# MCU_v2.net
KiCad netlist of a schematic drawn in EAGLE
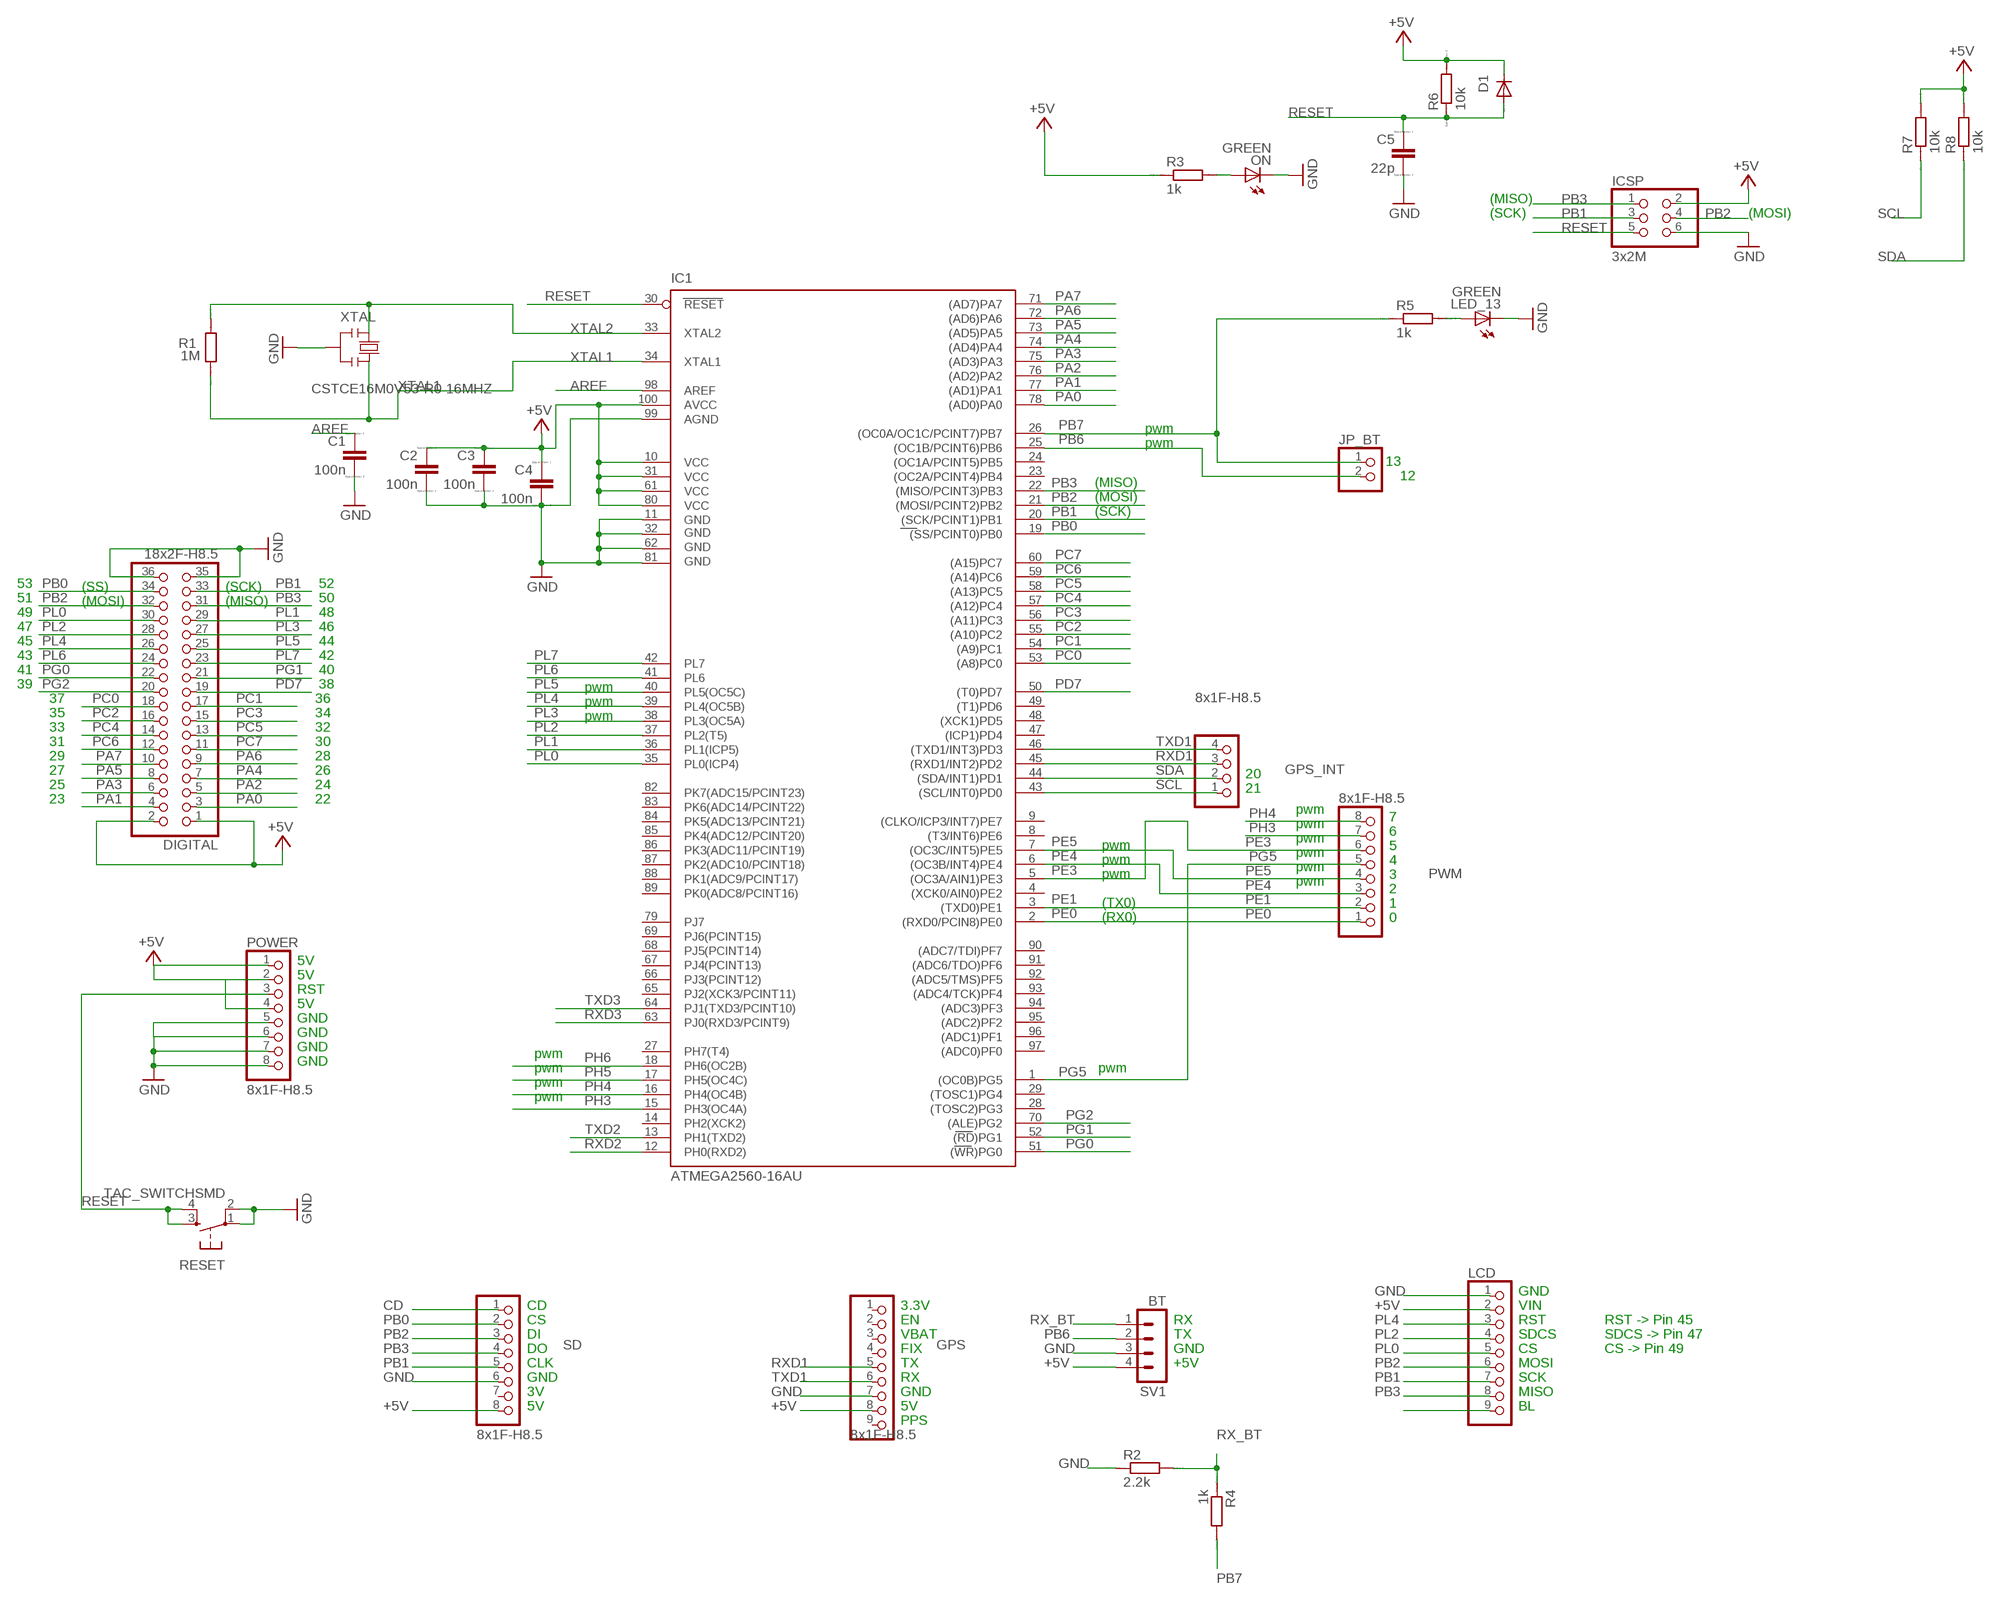
[diagram p0: schematic, sheet 1]

(export (version "E")
  (design (tool "Eeschema 10.0.6"))
  (components
    (comp (ref "C1")
      (value "100n")
      (footprint "eagle-import:C0805")
      (libsource (lib "eagle-import") (part "C-EUC0805"))
    )
    (comp (ref "C2")
      (value "100n")
      (footprint "eagle-import:C0805")
      (libsource (lib "eagle-import") (part "C-EUC0805"))
    )
    (comp (ref "C3")
      (value "100n")
      (footprint "eagle-import:C0805")
      (libsource (lib "eagle-import") (part "C-EUC0805"))
    )
    (comp (ref "C4")
      (value "100n")
      (footprint "eagle-import:C0805")
      (libsource (lib "eagle-import") (part "C-EUC0805"))
    )
    (comp (ref "C5")
      (value "22p")
      (footprint "eagle-import:C0805")
      (libsource (lib "eagle-import") (part "C-EUC0805"))
    )
    (comp (ref "D1")
      (value "DIODE-MINIMELF")
      (footprint "eagle-import:MINIMELF")
      (libsource (lib "eagle-import") (part "DIODE-MINIMELF"))
    )
    (comp (ref "DIGITAL")
      (value "18x2F-H8.5")
      (footprint "eagle-import:2X18")
      (libsource (lib "eagle-import") (part "PINHD-2X18"))
    )
    (comp (ref "GPS")
      (value "8x1F-H8.5")
      (footprint "eagle-import:1X09")
      (libsource (lib "eagle-import") (part "PINHD-1X9"))
    )
    (comp (ref "GPS_INT")
      (value "8x1F-H8.5")
      (footprint "eagle-import:1X04")
      (libsource (lib "eagle-import") (part "PINHD-1X4"))
    )
    (comp (ref "IC1")
      (value "ATMEGA2560-16AU")
      (footprint "eagle-import:TQFP100")
      (libsource (lib "eagle-import") (part "ATMEGA2560AU2560-16"))
    )
    (comp (ref "ICSP")
      (value "3x2M")
      (footprint "eagle-import:2X03")
      (libsource (lib "eagle-import") (part "PINHD-2X3"))
    )
    (comp (ref "JP_BT")
      (value "PINHD-1X2")
      (footprint "eagle-import:1X02")
      (libsource (lib "eagle-import") (part "PINHD-1X2"))
    )
    (comp (ref "LCD")
      (value "PINHD-1X9")
      (footprint "eagle-import:1X09")
      (libsource (lib "eagle-import") (part "PINHD-1X9"))
    )
    (comp (ref "LED_13")
      (value "GREEN")
      (footprint "eagle-import:CHIP-LED0805")
      (libsource (lib "eagle-import") (part "LEDCHIP-LED0805"))
    )
    (comp (ref "ON")
      (value "GREEN")
      (footprint "eagle-import:CHIP-LED0805")
      (libsource (lib "eagle-import") (part "LEDCHIP-LED0805"))
    )
    (comp (ref "POWER")
      (value "8x1F-H8.5")
      (footprint "eagle-import:1X08")
      (libsource (lib "eagle-import") (part "PINHD-1X8"))
    )
    (comp (ref "PWM")
      (value "8x1F-H8.5")
      (footprint "eagle-import:1X08")
      (libsource (lib "eagle-import") (part "PINHD-1X8"))
    )
    (comp (ref "R1")
      (value "1M")
      (footprint "eagle-import:R0805")
      (libsource (lib "eagle-import") (part "R-EU_R0805"))
    )
    (comp (ref "R2")
      (value "2.2k")
      (footprint "eagle-import:R0805")
      (libsource (lib "eagle-import") (part "R-EU_R0805"))
    )
    (comp (ref "R3")
      (value "1k")
      (footprint "eagle-import:R0805")
      (libsource (lib "eagle-import") (part "R-EU_R0805"))
    )
    (comp (ref "R4")
      (value "1k")
      (footprint "eagle-import:R0805")
      (libsource (lib "eagle-import") (part "R-EU_R0805"))
    )
    (comp (ref "R5")
      (value "1k")
      (footprint "eagle-import:R0805")
      (libsource (lib "eagle-import") (part "R-EU_R0805"))
    )
    (comp (ref "R6")
      (value "10k")
      (footprint "eagle-import:R0805")
      (libsource (lib "eagle-import") (part "R-EU_R0805"))
    )
    (comp (ref "R7")
      (value "10k")
      (footprint "eagle-import:R0805")
      (libsource (lib "eagle-import") (part "R-EU_R0805"))
    )
    (comp (ref "R8")
      (value "10k")
      (footprint "eagle-import:R0805")
      (libsource (lib "eagle-import") (part "R-EU_R0805"))
    )
    (comp (ref "RESET")
      (value "TAC_SWITCHSMD")
      (footprint "eagle-import:TACTILE-SWITCH-SMD")
      (libsource (lib "eagle-import") (part "TAC_SWITCHSMD"))
    )
    (comp (ref "SD")
      (value "8x1F-H8.5")
      (footprint "eagle-import:1X08")
      (libsource (lib "eagle-import") (part "PINHD-1X8"))
    )
    (comp (ref "SV1")
      (value "BT")
      (footprint "eagle-import:MA04-1")
      (libsource (lib "eagle-import") (part "MA04-1"))
    )
    (comp (ref "XTAL")
      (value "CSTCE16M0V53-R0 16MHZ")
      (footprint "eagle-import:RESONATOR")
      (libsource (lib "eagle-import") (part "RESONATORMU"))
    )
  )
  (nets
    (net (code "1") (name "+5V") (class "Default")
      (node (ref "C2") (pin "1") (pinfunction "1_1") (pintype "passive"))
      (node (ref "C3") (pin "1") (pinfunction "1_1") (pintype "passive"))
      (node (ref "C4") (pin "1") (pinfunction "1_1") (pintype "passive"))
      (node (ref "D1") (pin "C") (pinfunction "C_C") (pintype "passive"))
      (node (ref "DIGITAL") (pin "1") (pinfunction "1_1") (pintype "passive"))
      (node (ref "DIGITAL") (pin "2") (pinfunction "2_2") (pintype "passive"))
      (node (ref "GPS") (pin "8") (pinfunction "8_8") (pintype "passive"))
      (node (ref "IC1") (pin "10") (pinfunction "VCC_10") (pintype "power_in"))
      (node (ref "IC1") (pin "100") (pinfunction "AVCC_100") (pintype "power_in"))
      (node (ref "IC1") (pin "31") (pinfunction "VCC1_31") (pintype "power_in"))
      (node (ref "IC1") (pin "61") (pinfunction "VCC2_61") (pintype "power_in"))
      (node (ref "IC1") (pin "80") (pinfunction "VCC3_80") (pintype "power_in"))
      (node (ref "ICSP") (pin "2") (pinfunction "2_2") (pintype "passive"))
      (node (ref "LCD") (pin "2") (pinfunction "2_2") (pintype "passive"))
      (node (ref "POWER") (pin "1") (pinfunction "1_1") (pintype "passive"))
      (node (ref "POWER") (pin "2") (pinfunction "2_2") (pintype "passive"))
      (node (ref "POWER") (pin "4") (pinfunction "4_4") (pintype "passive"))
      (node (ref "R3") (pin "1") (pinfunction "1_1") (pintype "passive"))
      (node (ref "R6") (pin "2") (pinfunction "2_2") (pintype "passive"))
      (node (ref "R7") (pin "2") (pinfunction "2_2") (pintype "passive"))
      (node (ref "R8") (pin "2") (pinfunction "2_2") (pintype "passive"))
      (node (ref "SD") (pin "8") (pinfunction "8_8") (pintype "passive"))
      (node (ref "SV1") (pin "4") (pinfunction "4_4") (pintype "passive"))
    )
    (net (code "2") (name "/AREF") (class "Default")
      (node (ref "C1") (pin "1") (pinfunction "1_1") (pintype "passive"))
      (node (ref "IC1") (pin "98") (pinfunction "AREF_98") (pintype "bidirectional"))
    )
    (net (code "3") (name "/CD") (class "Default")
      (node (ref "SD") (pin "1") (pinfunction "1_1") (pintype "passive"))
    )
    (net (code "4") (name "/PA0") (class "Default")
      (node (ref "DIGITAL") (pin "3") (pinfunction "3_3") (pintype "passive"))
      (node (ref "IC1") (pin "78") (pinfunction "(AD0)PA0_78") (pintype "bidirectional"))
    )
    (net (code "5") (name "/PA1") (class "Default")
      (node (ref "DIGITAL") (pin "4") (pinfunction "4_4") (pintype "passive"))
      (node (ref "IC1") (pin "77") (pinfunction "(AD1)PA1_77") (pintype "bidirectional"))
    )
    (net (code "6") (name "/PA2") (class "Default")
      (node (ref "DIGITAL") (pin "5") (pinfunction "5_5") (pintype "passive"))
      (node (ref "IC1") (pin "76") (pinfunction "(AD2)PA2_76") (pintype "bidirectional"))
    )
    (net (code "7") (name "/PA3") (class "Default")
      (node (ref "DIGITAL") (pin "6") (pinfunction "6_6") (pintype "passive"))
      (node (ref "IC1") (pin "75") (pinfunction "(AD3)PA3_75") (pintype "bidirectional"))
    )
    (net (code "8") (name "/PA4") (class "Default")
      (node (ref "DIGITAL") (pin "7") (pinfunction "7_7") (pintype "passive"))
      (node (ref "IC1") (pin "74") (pinfunction "(AD4)PA4_74") (pintype "bidirectional"))
    )
    (net (code "9") (name "/PA5") (class "Default")
      (node (ref "DIGITAL") (pin "8") (pinfunction "8_8") (pintype "passive"))
      (node (ref "IC1") (pin "73") (pinfunction "(AD5)PA5_73") (pintype "bidirectional"))
    )
    (net (code "10") (name "/PA6") (class "Default")
      (node (ref "DIGITAL") (pin "9") (pinfunction "9_9") (pintype "passive"))
      (node (ref "IC1") (pin "72") (pinfunction "(AD6)PA6_72") (pintype "bidirectional"))
    )
    (net (code "11") (name "/PA7") (class "Default")
      (node (ref "DIGITAL") (pin "10") (pinfunction "10_10") (pintype "passive"))
      (node (ref "IC1") (pin "71") (pinfunction "(AD7)PA7_71") (pintype "bidirectional"))
    )
    (net (code "12") (name "/PB0") (class "Default")
      (node (ref "DIGITAL") (pin "34") (pinfunction "34_34") (pintype "passive"))
      (node (ref "IC1") (pin "19") (pinfunction "(SS/PCINT0)PB0_19") (pintype "bidirectional"))
      (node (ref "SD") (pin "2") (pinfunction "2_2") (pintype "passive"))
    )
    (net (code "13") (name "/PB1") (class "Default")
      (node (ref "DIGITAL") (pin "33") (pinfunction "33_33") (pintype "passive"))
      (node (ref "IC1") (pin "20") (pinfunction "(SCK/PCINT1)PB1_20") (pintype "bidirectional"))
      (node (ref "ICSP") (pin "3") (pinfunction "3_3") (pintype "passive"))
      (node (ref "LCD") (pin "7") (pinfunction "7_7") (pintype "passive"))
      (node (ref "SD") (pin "5") (pinfunction "5_5") (pintype "passive"))
    )
    (net (code "14") (name "/PB2") (class "Default")
      (node (ref "DIGITAL") (pin "32") (pinfunction "32_32") (pintype "passive"))
      (node (ref "IC1") (pin "21") (pinfunction "(MOSI/PCINT2)PB2_21") (pintype "bidirectional"))
      (node (ref "ICSP") (pin "4") (pinfunction "4_4") (pintype "passive"))
      (node (ref "LCD") (pin "6") (pinfunction "6_6") (pintype "passive"))
      (node (ref "SD") (pin "3") (pinfunction "3_3") (pintype "passive"))
    )
    (net (code "15") (name "/PB3") (class "Default")
      (node (ref "DIGITAL") (pin "31") (pinfunction "31_31") (pintype "passive"))
      (node (ref "IC1") (pin "22") (pinfunction "(MISO/PCINT3)PB3_22") (pintype "bidirectional"))
      (node (ref "ICSP") (pin "1") (pinfunction "1_1") (pintype "passive"))
      (node (ref "LCD") (pin "8") (pinfunction "8_8") (pintype "passive"))
      (node (ref "SD") (pin "4") (pinfunction "4_4") (pintype "passive"))
    )
    (net (code "16") (name "/PB6") (class "Default")
      (node (ref "IC1") (pin "25") (pinfunction "(OC1B/PCINT6)PB6_25") (pintype "bidirectional"))
      (node (ref "JP_BT") (pin "2") (pinfunction "2_2") (pintype "passive"))
      (node (ref "SV1") (pin "2") (pinfunction "2_2") (pintype "passive"))
    )
    (net (code "17") (name "/PB7") (class "Default")
      (node (ref "IC1") (pin "26") (pinfunction "(OC0A/OC1C/PCINT7)PB7_26") (pintype "bidirectional"))
      (node (ref "JP_BT") (pin "1") (pinfunction "1_1") (pintype "passive"))
      (node (ref "R4") (pin "2") (pinfunction "2_2") (pintype "passive"))
      (node (ref "R5") (pin "1") (pinfunction "1_1") (pintype "passive"))
    )
    (net (code "18") (name "/PC0") (class "Default")
      (node (ref "DIGITAL") (pin "18") (pinfunction "18_18") (pintype "passive"))
      (node (ref "IC1") (pin "53") (pinfunction "(A8)PC0_53") (pintype "bidirectional"))
    )
    (net (code "19") (name "/PC1") (class "Default")
      (node (ref "DIGITAL") (pin "17") (pinfunction "17_17") (pintype "passive"))
      (node (ref "IC1") (pin "54") (pinfunction "(A9)PC1_54") (pintype "bidirectional"))
    )
    (net (code "20") (name "/PC2") (class "Default")
      (node (ref "DIGITAL") (pin "16") (pinfunction "16_16") (pintype "passive"))
      (node (ref "IC1") (pin "55") (pinfunction "(A10)PC2_55") (pintype "bidirectional"))
    )
    (net (code "21") (name "/PC3") (class "Default")
      (node (ref "DIGITAL") (pin "15") (pinfunction "15_15") (pintype "passive"))
      (node (ref "IC1") (pin "56") (pinfunction "(A11)PC3_56") (pintype "bidirectional"))
    )
    (net (code "22") (name "/PC4") (class "Default")
      (node (ref "DIGITAL") (pin "14") (pinfunction "14_14") (pintype "passive"))
      (node (ref "IC1") (pin "57") (pinfunction "(A12)PC4_57") (pintype "bidirectional"))
    )
    (net (code "23") (name "/PC5") (class "Default")
      (node (ref "DIGITAL") (pin "13") (pinfunction "13_13") (pintype "passive"))
      (node (ref "IC1") (pin "58") (pinfunction "(A13)PC5_58") (pintype "bidirectional"))
    )
    (net (code "24") (name "/PC6") (class "Default")
      (node (ref "DIGITAL") (pin "12") (pinfunction "12_12") (pintype "passive"))
      (node (ref "IC1") (pin "59") (pinfunction "(A14)PC6_59") (pintype "bidirectional"))
    )
    (net (code "25") (name "/PC7") (class "Default")
      (node (ref "DIGITAL") (pin "11") (pinfunction "11_11") (pintype "passive"))
      (node (ref "IC1") (pin "60") (pinfunction "(A15)PC7_60") (pintype "bidirectional"))
    )
    (net (code "26") (name "/PD7") (class "Default")
      (node (ref "DIGITAL") (pin "19") (pinfunction "19_19") (pintype "passive"))
      (node (ref "IC1") (pin "50") (pinfunction "(T0)PD7_50") (pintype "bidirectional"))
    )
    (net (code "27") (name "/PE0") (class "Default")
      (node (ref "IC1") (pin "2") (pinfunction "(RXD0/PCIN8)PE0_2") (pintype "bidirectional"))
      (node (ref "PWM") (pin "1") (pinfunction "1_1") (pintype "passive"))
    )
    (net (code "28") (name "/PE1") (class "Default")
      (node (ref "IC1") (pin "3") (pinfunction "(TXD0)PE1_3") (pintype "bidirectional"))
      (node (ref "PWM") (pin "2") (pinfunction "2_2") (pintype "passive"))
    )
    (net (code "29") (name "/PE3") (class "Default")
      (node (ref "IC1") (pin "5") (pinfunction "(OC3A/AIN1)PE3_5") (pintype "bidirectional"))
      (node (ref "PWM") (pin "6") (pinfunction "6_6") (pintype "passive"))
    )
    (net (code "30") (name "/PE4") (class "Default")
      (node (ref "IC1") (pin "6") (pinfunction "(OC3B/INT4)PE4_6") (pintype "bidirectional"))
      (node (ref "PWM") (pin "3") (pinfunction "3_3") (pintype "passive"))
    )
    (net (code "31") (name "/PE5") (class "Default")
      (node (ref "IC1") (pin "7") (pinfunction "(OC3C/INT5)PE5_7") (pintype "bidirectional"))
      (node (ref "PWM") (pin "4") (pinfunction "4_4") (pintype "passive"))
    )
    (net (code "32") (name "/PG0") (class "Default")
      (node (ref "DIGITAL") (pin "22") (pinfunction "22_22") (pintype "passive"))
      (node (ref "IC1") (pin "51") (pinfunction "(WR)PG0_51") (pintype "bidirectional"))
    )
    (net (code "33") (name "/PG1") (class "Default")
      (node (ref "DIGITAL") (pin "21") (pinfunction "21_21") (pintype "passive"))
      (node (ref "IC1") (pin "52") (pinfunction "(RD)PG1_52") (pintype "bidirectional"))
    )
    (net (code "34") (name "/PG2") (class "Default")
      (node (ref "DIGITAL") (pin "20") (pinfunction "20_20") (pintype "passive"))
      (node (ref "IC1") (pin "70") (pinfunction "(ALE)PG2_70") (pintype "bidirectional"))
    )
    (net (code "35") (name "/PG5") (class "Default")
      (node (ref "IC1") (pin "1") (pinfunction "(OC0B)PG5_1") (pintype "bidirectional"))
      (node (ref "PWM") (pin "5") (pinfunction "5_5") (pintype "passive"))
    )
    (net (code "36") (name "/PH3") (class "Default")
      (node (ref "IC1") (pin "15") (pinfunction "PH3(OC4A)_15") (pintype "bidirectional"))
      (node (ref "PWM") (pin "7") (pinfunction "7_7") (pintype "passive"))
    )
    (net (code "37") (name "/PH4") (class "Default")
      (node (ref "IC1") (pin "16") (pinfunction "PH4(OC4B)_16") (pintype "bidirectional"))
      (node (ref "PWM") (pin "8") (pinfunction "8_8") (pintype "passive"))
    )
    (net (code "38") (name "/PH5") (class "Default")
      (node (ref "IC1") (pin "17") (pinfunction "PH5(OC4C)_17") (pintype "bidirectional"))
    )
    (net (code "39") (name "/PH6") (class "Default")
      (node (ref "IC1") (pin "18") (pinfunction "PH6(OC2B)_18") (pintype "bidirectional"))
    )
    (net (code "40") (name "/PL0") (class "Default")
      (node (ref "DIGITAL") (pin "30") (pinfunction "30_30") (pintype "passive"))
      (node (ref "IC1") (pin "35") (pinfunction "PL0(ICP4)_35") (pintype "bidirectional"))
      (node (ref "LCD") (pin "5") (pinfunction "5_5") (pintype "passive"))
    )
    (net (code "41") (name "/PL1") (class "Default")
      (node (ref "DIGITAL") (pin "29") (pinfunction "29_29") (pintype "passive"))
      (node (ref "IC1") (pin "36") (pinfunction "PL1(ICP5)_36") (pintype "bidirectional"))
    )
    (net (code "42") (name "/PL2") (class "Default")
      (node (ref "DIGITAL") (pin "28") (pinfunction "28_28") (pintype "passive"))
      (node (ref "IC1") (pin "37") (pinfunction "PL2(T5)_37") (pintype "bidirectional"))
      (node (ref "LCD") (pin "4") (pinfunction "4_4") (pintype "passive"))
    )
    (net (code "43") (name "/PL3") (class "Default")
      (node (ref "DIGITAL") (pin "27") (pinfunction "27_27") (pintype "passive"))
      (node (ref "IC1") (pin "38") (pinfunction "PL3(OC5A)_38") (pintype "bidirectional"))
    )
    (net (code "44") (name "/PL4") (class "Default")
      (node (ref "DIGITAL") (pin "26") (pinfunction "26_26") (pintype "passive"))
      (node (ref "IC1") (pin "39") (pinfunction "PL4(OC5B)_39") (pintype "bidirectional"))
      (node (ref "LCD") (pin "3") (pinfunction "3_3") (pintype "passive"))
    )
    (net (code "45") (name "/PL5") (class "Default")
      (node (ref "DIGITAL") (pin "25") (pinfunction "25_25") (pintype "passive"))
      (node (ref "IC1") (pin "40") (pinfunction "PL5(OC5C)_40") (pintype "bidirectional"))
    )
    (net (code "46") (name "/PL6") (class "Default")
      (node (ref "DIGITAL") (pin "24") (pinfunction "24_24") (pintype "passive"))
      (node (ref "IC1") (pin "41") (pinfunction "PL6_41") (pintype "bidirectional"))
    )
    (net (code "47") (name "/PL7") (class "Default")
      (node (ref "DIGITAL") (pin "23") (pinfunction "23_23") (pintype "passive"))
      (node (ref "IC1") (pin "42") (pinfunction "PL7_42") (pintype "bidirectional"))
    )
    (net (code "48") (name "/RESET") (class "Default")
      (node (ref "C5") (pin "1") (pinfunction "1_1") (pintype "passive"))
      (node (ref "D1") (pin "A") (pinfunction "A_A") (pintype "passive"))
      (node (ref "IC1") (pin "30") (pinfunction "RESET_30") (pintype "input"))
      (node (ref "ICSP") (pin "5") (pinfunction "5_5") (pintype "passive"))
      (node (ref "POWER") (pin "3") (pinfunction "3_3") (pintype "passive"))
      (node (ref "R6") (pin "1") (pinfunction "1_1") (pintype "passive"))
      (node (ref "RESET") (pin "3") (pinfunction "3_3") (pintype "passive"))
      (node (ref "RESET") (pin "4") (pinfunction "4_4") (pintype "passive"))
    )
    (net (code "49") (name "/RXD1") (class "Default")
      (node (ref "GPS") (pin "5") (pinfunction "5_5") (pintype "passive"))
      (node (ref "GPS_INT") (pin "3") (pinfunction "3_3") (pintype "passive"))
      (node (ref "IC1") (pin "45") (pinfunction "(RXD1/INT2)PD2_45") (pintype "bidirectional"))
    )
    (net (code "50") (name "/RXD2") (class "Default")
      (node (ref "IC1") (pin "12") (pinfunction "PH0(RXD2)_12") (pintype "bidirectional"))
    )
    (net (code "51") (name "/RXD3") (class "Default")
      (node (ref "IC1") (pin "63") (pinfunction "PJ0(RXD3/PCINT9)_63") (pintype "bidirectional"))
    )
    (net (code "52") (name "/RX_BT") (class "Default")
      (node (ref "R2") (pin "2") (pinfunction "2_2") (pintype "passive"))
      (node (ref "R4") (pin "1") (pinfunction "1_1") (pintype "passive"))
      (node (ref "SV1") (pin "1") (pinfunction "1_1") (pintype "passive"))
    )
    (net (code "53") (name "/SCL") (class "Default")
      (node (ref "GPS_INT") (pin "1") (pinfunction "1_1") (pintype "passive"))
      (node (ref "IC1") (pin "43") (pinfunction "(SCL/INT0)PD0_43") (pintype "bidirectional"))
      (node (ref "R7") (pin "1") (pinfunction "1_1") (pintype "passive"))
    )
    (net (code "54") (name "/SDA") (class "Default")
      (node (ref "GPS_INT") (pin "2") (pinfunction "2_2") (pintype "passive"))
      (node (ref "IC1") (pin "44") (pinfunction "(SDA/INT1)PD1_44") (pintype "bidirectional"))
      (node (ref "R8") (pin "1") (pinfunction "1_1") (pintype "passive"))
    )
    (net (code "55") (name "/TXD1") (class "Default")
      (node (ref "GPS") (pin "6") (pinfunction "6_6") (pintype "passive"))
      (node (ref "GPS_INT") (pin "4") (pinfunction "4_4") (pintype "passive"))
      (node (ref "IC1") (pin "46") (pinfunction "(TXD1/INT3)PD3_46") (pintype "bidirectional"))
    )
    (net (code "56") (name "/TXD2") (class "Default")
      (node (ref "IC1") (pin "13") (pinfunction "PH1(TXD2)_13") (pintype "bidirectional"))
    )
    (net (code "57") (name "/TXD3") (class "Default")
      (node (ref "IC1") (pin "64") (pinfunction "PJ1(TXD3/PCINT10)_64") (pintype "bidirectional"))
    )
    (net (code "58") (name "/XTAL1") (class "Default")
      (node (ref "IC1") (pin "34") (pinfunction "XTAL1_34") (pintype "input"))
      (node (ref "R1") (pin "1") (pinfunction "1_1") (pintype "passive"))
      (node (ref "XTAL") (pin "3") (pinfunction "3_3") (pintype "passive"))
    )
    (net (code "59") (name "/XTAL2") (class "Default")
      (node (ref "IC1") (pin "33") (pinfunction "XTAL2_33") (pintype "output"))
      (node (ref "R1") (pin "2") (pinfunction "2_2") (pintype "passive"))
      (node (ref "XTAL") (pin "1") (pinfunction "1_1") (pintype "passive"))
    )
    (net (code "60") (name "GND") (class "Default")
      (node (ref "C1") (pin "2") (pinfunction "2_2") (pintype "passive"))
      (node (ref "C2") (pin "2") (pinfunction "2_2") (pintype "passive"))
      (node (ref "C3") (pin "2") (pinfunction "2_2") (pintype "passive"))
      (node (ref "C4") (pin "2") (pinfunction "2_2") (pintype "passive"))
      (node (ref "C5") (pin "2") (pinfunction "2_2") (pintype "passive"))
      (node (ref "DIGITAL") (pin "35") (pinfunction "35_35") (pintype "passive"))
      (node (ref "DIGITAL") (pin "36") (pinfunction "36_36") (pintype "passive"))
      (node (ref "GPS") (pin "7") (pinfunction "7_7") (pintype "passive"))
      (node (ref "IC1") (pin "11") (pinfunction "GND_11") (pintype "power_in"))
      (node (ref "IC1") (pin "32") (pinfunction "GND1_32") (pintype "power_in"))
      (node (ref "IC1") (pin "62") (pinfunction "GND2_62") (pintype "power_in"))
      (node (ref "IC1") (pin "81") (pinfunction "GND3_81") (pintype "power_in"))
      (node (ref "IC1") (pin "99") (pinfunction "AGND_99") (pintype "power_in"))
      (node (ref "ICSP") (pin "6") (pinfunction "6_6") (pintype "passive"))
      (node (ref "LCD") (pin "1") (pinfunction "1_1") (pintype "passive"))
      (node (ref "LED_13") (pin "C") (pinfunction "C_C") (pintype "passive"))
      (node (ref "ON") (pin "C") (pinfunction "C_C") (pintype "passive"))
      (node (ref "POWER") (pin "5") (pinfunction "5_5") (pintype "passive"))
      (node (ref "POWER") (pin "6") (pinfunction "6_6") (pintype "passive"))
      (node (ref "POWER") (pin "7") (pinfunction "7_7") (pintype "passive"))
      (node (ref "POWER") (pin "8") (pinfunction "8_8") (pintype "passive"))
      (node (ref "R2") (pin "1") (pinfunction "1_1") (pintype "passive"))
      (node (ref "RESET") (pin "1") (pinfunction "1_1") (pintype "passive"))
      (node (ref "RESET") (pin "2") (pinfunction "2_2") (pintype "passive"))
      (node (ref "SD") (pin "6") (pinfunction "6_6") (pintype "passive"))
      (node (ref "SV1") (pin "3") (pinfunction "3_3") (pintype "passive"))
      (node (ref "XTAL") (pin "2") (pinfunction "2_2") (pintype "passive"))
    )
    (net (code "61") (name "Net-(LED_13-PadA)") (class "Default")
      (node (ref "LED_13") (pin "A") (pinfunction "A_A") (pintype "passive"))
      (node (ref "R5") (pin "2") (pinfunction "2_2") (pintype "passive"))
    )
    (net (code "62") (name "Net-(ON-PadA)") (class "Default")
      (node (ref "ON") (pin "A") (pinfunction "A_A") (pintype "passive"))
      (node (ref "R3") (pin "2") (pinfunction "2_2") (pintype "passive"))
    )
    (net (code "63") (name "unconnected-(GPS-Pad1)") (class "Default")
      (node (ref "GPS") (pin "1") (pinfunction "1_1") (pintype "passive"))
    )
    (net (code "64") (name "unconnected-(GPS-Pad2)") (class "Default")
      (node (ref "GPS") (pin "2") (pinfunction "2_2") (pintype "passive"))
    )
    (net (code "65") (name "unconnected-(GPS-Pad3)") (class "Default")
      (node (ref "GPS") (pin "3") (pinfunction "3_3") (pintype "passive"))
    )
    (net (code "66") (name "unconnected-(GPS-Pad4)") (class "Default")
      (node (ref "GPS") (pin "4") (pinfunction "4_4") (pintype "passive"))
    )
    (net (code "67") (name "unconnected-(GPS-Pad9)") (class "Default")
      (node (ref "GPS") (pin "9") (pinfunction "9_9") (pintype "passive"))
    )
    (net (code "68") (name "unconnected-(IC1-(ADC0)PF0-Pad97)") (class "Default")
      (node (ref "IC1") (pin "97") (pinfunction "(ADC0)PF0_97") (pintype "bidirectional"))
    )
    (net (code "69") (name "unconnected-(IC1-(ADC1)PF1-Pad96)") (class "Default")
      (node (ref "IC1") (pin "96") (pinfunction "(ADC1)PF1_96") (pintype "bidirectional"))
    )
    (net (code "70") (name "unconnected-(IC1-(ADC2)PF2-Pad95)") (class "Default")
      (node (ref "IC1") (pin "95") (pinfunction "(ADC2)PF2_95") (pintype "bidirectional"))
    )
    (net (code "71") (name "unconnected-(IC1-(ADC3)PF3-Pad94)") (class "Default")
      (node (ref "IC1") (pin "94") (pinfunction "(ADC3)PF3_94") (pintype "bidirectional"))
    )
    (net (code "72") (name "unconnected-(IC1-(ADC4{slash}TCK)PF4-Pad93)") (class "Default")
      (node (ref "IC1") (pin "93") (pinfunction "(ADC4/TCK)PF4_93") (pintype "bidirectional"))
    )
    (net (code "73") (name "unconnected-(IC1-(ADC5{slash}TMS)PF5-Pad92)") (class "Default")
      (node (ref "IC1") (pin "92") (pinfunction "(ADC5/TMS)PF5_92") (pintype "bidirectional"))
    )
    (net (code "74") (name "unconnected-(IC1-(ADC6{slash}TDO)PF6-Pad91)") (class "Default")
      (node (ref "IC1") (pin "91") (pinfunction "(ADC6/TDO)PF6_91") (pintype "bidirectional"))
    )
    (net (code "75") (name "unconnected-(IC1-(ADC7{slash}TDI)PF7-Pad90)") (class "Default")
      (node (ref "IC1") (pin "90") (pinfunction "(ADC7/TDI)PF7_90") (pintype "bidirectional"))
    )
    (net (code "76") (name "unconnected-(IC1-(CLKO{slash}ICP3{slash}INT7)PE7-Pad9)") (class "Default")
      (node (ref "IC1") (pin "9") (pinfunction "(CLKO/ICP3/INT7)PE7_9") (pintype "bidirectional"))
    )
    (net (code "77") (name "unconnected-(IC1-(ICP1)PD4-Pad47)") (class "Default")
      (node (ref "IC1") (pin "47") (pinfunction "(ICP1)PD4_47") (pintype "bidirectional"))
    )
    (net (code "78") (name "unconnected-(IC1-(OC1A{slash}PCINT5)PB5-Pad24)") (class "Default")
      (node (ref "IC1") (pin "24") (pinfunction "(OC1A/PCINT5)PB5_24") (pintype "bidirectional"))
    )
    (net (code "79") (name "unconnected-(IC1-(OC2A{slash}PCINT4)PB4-Pad23)") (class "Default")
      (node (ref "IC1") (pin "23") (pinfunction "(OC2A/PCINT4)PB4_23") (pintype "bidirectional"))
    )
    (net (code "80") (name "unconnected-(IC1-(T1)PD6-Pad49)") (class "Default")
      (node (ref "IC1") (pin "49") (pinfunction "(T1)PD6_49") (pintype "bidirectional"))
    )
    (net (code "81") (name "unconnected-(IC1-(T3{slash}INT6)PE6-Pad8)") (class "Default")
      (node (ref "IC1") (pin "8") (pinfunction "(T3/INT6)PE6_8") (pintype "bidirectional"))
    )
    (net (code "82") (name "unconnected-(IC1-(TOSC1)PG4-Pad29)") (class "Default")
      (node (ref "IC1") (pin "29") (pinfunction "(TOSC1)PG4_29") (pintype "bidirectional"))
    )
    (net (code "83") (name "unconnected-(IC1-(TOSC2)PG3-Pad28)") (class "Default")
      (node (ref "IC1") (pin "28") (pinfunction "(TOSC2)PG3_28") (pintype "bidirectional"))
    )
    (net (code "84") (name "unconnected-(IC1-(XCK0{slash}AIN0)PE2-Pad4)") (class "Default")
      (node (ref "IC1") (pin "4") (pinfunction "(XCK0/AIN0)PE2_4") (pintype "bidirectional"))
    )
    (net (code "85") (name "unconnected-(IC1-(XCK1)PD5-Pad48)") (class "Default")
      (node (ref "IC1") (pin "48") (pinfunction "(XCK1)PD5_48") (pintype "bidirectional"))
    )
    (net (code "86") (name "unconnected-(IC1-PH2(XCK2)-Pad14)") (class "Default")
      (node (ref "IC1") (pin "14") (pinfunction "PH2(XCK2)_14") (pintype "bidirectional"))
    )
    (net (code "87") (name "unconnected-(IC1-PH7(T4)-Pad27)") (class "Default")
      (node (ref "IC1") (pin "27") (pinfunction "PH7(T4)_27") (pintype "bidirectional"))
    )
    (net (code "88") (name "unconnected-(IC1-PJ2(XCK3{slash}PCINT11)-Pad65)") (class "Default")
      (node (ref "IC1") (pin "65") (pinfunction "PJ2(XCK3/PCINT11)_65") (pintype "bidirectional"))
    )
    (net (code "89") (name "unconnected-(IC1-PJ3(PCINT12)-Pad66)") (class "Default")
      (node (ref "IC1") (pin "66") (pinfunction "PJ3(PCINT12)_66") (pintype "bidirectional"))
    )
    (net (code "90") (name "unconnected-(IC1-PJ4(PCINT13)-Pad67)") (class "Default")
      (node (ref "IC1") (pin "67") (pinfunction "PJ4(PCINT13)_67") (pintype "bidirectional"))
    )
    (net (code "91") (name "unconnected-(IC1-PJ5(PCINT14)-Pad68)") (class "Default")
      (node (ref "IC1") (pin "68") (pinfunction "PJ5(PCINT14)_68") (pintype "bidirectional"))
    )
    (net (code "92") (name "unconnected-(IC1-PJ6(PCINT15)-Pad69)") (class "Default")
      (node (ref "IC1") (pin "69") (pinfunction "PJ6(PCINT15)_69") (pintype "bidirectional"))
    )
    (net (code "93") (name "unconnected-(IC1-PJ7-Pad79)") (class "Default")
      (node (ref "IC1") (pin "79") (pinfunction "PJ7_79") (pintype "bidirectional"))
    )
    (net (code "94") (name "unconnected-(IC1-PK0(ADC8{slash}PCINT16)-Pad89)") (class "Default")
      (node (ref "IC1") (pin "89") (pinfunction "PK0(ADC8/PCINT16)_89") (pintype "bidirectional"))
    )
    (net (code "95") (name "unconnected-(IC1-PK1(ADC9{slash}PCINT17)-Pad88)") (class "Default")
      (node (ref "IC1") (pin "88") (pinfunction "PK1(ADC9/PCINT17)_88") (pintype "bidirectional"))
    )
    (net (code "96") (name "unconnected-(IC1-PK2(ADC10{slash}PCINT18)-Pad87)") (class "Default")
      (node (ref "IC1") (pin "87") (pinfunction "PK2(ADC10/PCINT18)_87") (pintype "bidirectional"))
    )
    (net (code "97") (name "unconnected-(IC1-PK3(ADC11{slash}PCINT19)-Pad86)") (class "Default")
      (node (ref "IC1") (pin "86") (pinfunction "PK3(ADC11/PCINT19)_86") (pintype "bidirectional"))
    )
    (net (code "98") (name "unconnected-(IC1-PK4(ADC12{slash}PCINT20)-Pad85)") (class "Default")
      (node (ref "IC1") (pin "85") (pinfunction "PK4(ADC12/PCINT20)_85") (pintype "bidirectional"))
    )
    (net (code "99") (name "unconnected-(IC1-PK5(ADC13{slash}PCINT21)-Pad84)") (class "Default")
      (node (ref "IC1") (pin "84") (pinfunction "PK5(ADC13/PCINT21)_84") (pintype "bidirectional"))
    )
    (net (code "100") (name "unconnected-(IC1-PK6(ADC14{slash}PCINT22)-Pad83)") (class "Default")
      (node (ref "IC1") (pin "83") (pinfunction "PK6(ADC14/PCINT22)_83") (pintype "bidirectional"))
    )
    (net (code "101") (name "unconnected-(IC1-PK7(ADC15{slash}PCINT23)-Pad82)") (class "Default")
      (node (ref "IC1") (pin "82") (pinfunction "PK7(ADC15/PCINT23)_82") (pintype "bidirectional"))
    )
    (net (code "102") (name "unconnected-(LCD-Pad9)") (class "Default")
      (node (ref "LCD") (pin "9") (pinfunction "9_9") (pintype "passive"))
    )
    (net (code "103") (name "unconnected-(SD-Pad7)") (class "Default")
      (node (ref "SD") (pin "7") (pinfunction "7_7") (pintype "passive"))
    )
  )
)
